# 1.net
KiCad netlist of a schematic drawn in Altium Designer
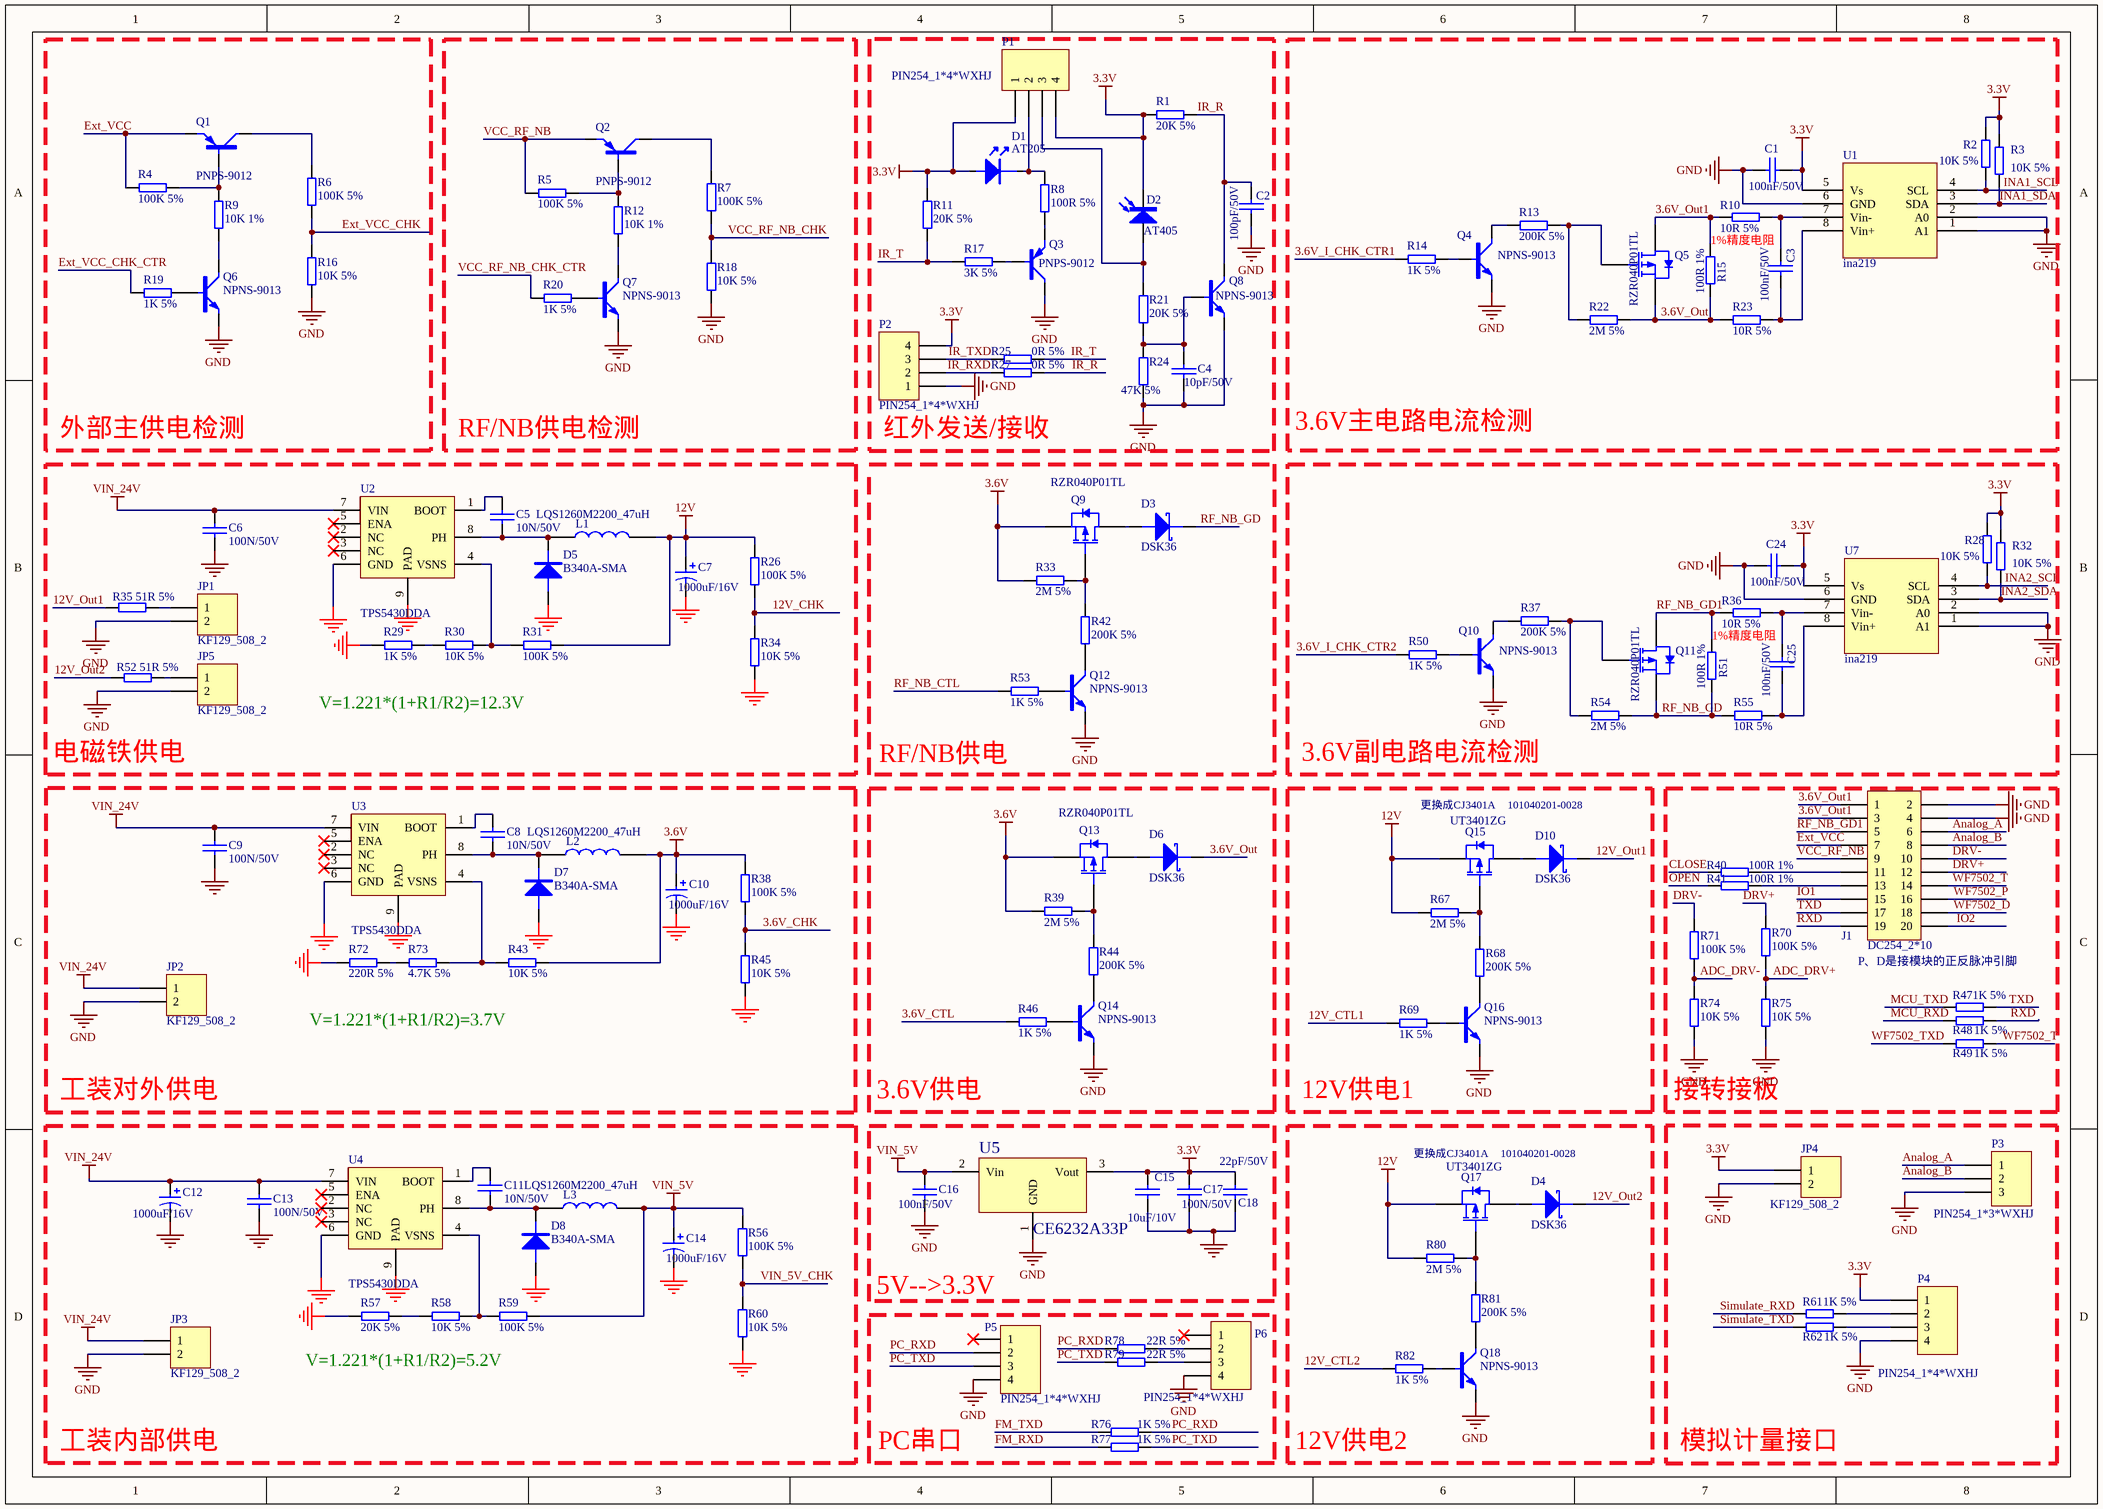
[diagram p0: 水表通用工装一版1.SchDoc]

(export (version "E")
  (design (tool "Eeschema 10.0.6"))
  (components
    (comp (ref "C1")
      (value "100nF/50V")
      (footprint "CAP0603")
      (description "104pF,50 V,±10%,0603,国巨,CC0603KRX7R9BB104")
      (fields (field (name "PART NUMBER") "101020103-0021"))
      (libsource (lib "Database_Libs2") (part "CC03K7R9_100N"))
    )
    (comp (ref "C2")
      (value "100pF/50V")
      (footprint "CAP0603")
      (description "101pf,50 V,±5%,0603,国巨,CC0603JRNP09BN101")
      (fields (field (name "PART NUMBER") "101020103-0010"))
      (libsource (lib "Database_Libs2") (part "CC03JPO9_101P"))
    )
    (comp (ref "C3")
      (value "100nF/50V")
      (footprint "CAP0603")
      (description "104pF,50 V,±10%,0603,国巨,CC0603KRX7R9BB104")
      (fields (field (name "PART NUMBER") "101020103-0021"))
      (libsource (lib "Database_Libs2") (part "CC03K7R9_100N"))
    )
    (comp (ref "C4")
      (value "10pF/50V")
      (footprint "CAP0603")
      (description "10pF,50 V,±5%,0603,X7R,国巨,CC0603JRNPO9BN100")
      (fields (field (name "PART NUMBER") "101020103-0014"))
      (libsource (lib "Database_Libs2") (part "CC03JPO9_10P"))
    )
    (comp (ref "C5")
      (value "10N/50V")
      (footprint "CAP0603")
      (description "10N/50V，±10%，0603")
      (fields (field (name "PART NUMBER") "101020103-0007"))
      (libsource (lib "Database_Libs1") (part "CC03K7R9B_10N"))
    )
    (comp (ref "C6")
      (value "100N/50V")
      (footprint "CAP0603")
      (description "100N/50V，±10%，0603")
      (fields (field (name "PART NUMBER") "101020103-0021"))
      (libsource (lib "Database_Libs1") (part "CC03K7R9B_100N"))
    )
    (comp (ref "C7")
      (value "1000uF/16V")
      (footprint "CAPPC_350_800_1600")
      (description "1000uF,16 V,±20%,8*20mm,Rubycon,16ZLH1000M")
      (fields (field (name "PART NUMBER") "1010203-0029"))
      (libsource (lib "Database_Libs2") (part "CAL7MRZLH_1000U_R"))
    )
    (comp (ref "C8")
      (value "10N/50V")
      (footprint "CAP0603")
      (description "10N/50V，±10%，0603")
      (fields (field (name "PART NUMBER") "101020103-0007"))
      (libsource (lib "Database_Libs1") (part "CC03K7R9B_10N"))
    )
    (comp (ref "C9")
      (value "100N/50V")
      (footprint "CAP0603")
      (description "100N/50V，±10%，0603")
      (fields (field (name "PART NUMBER") "101020103-0021"))
      (libsource (lib "Database_Libs1") (part "CC03K7R9B_100N"))
    )
    (comp (ref "C10")
      (value "1000uF/16V")
      (footprint "CAPPC_350_800_1600")
      (description "1000uF,16 V,±20%,8*20mm,Rubycon,16ZLH1000M")
      (fields (field (name "PART NUMBER") "1010203-0029"))
      (libsource (lib "Database_Libs2") (part "CAL7MRZLH_1000U_R"))
    )
    (comp (ref "C11")
      (value "10N/50V")
      (footprint "CAP0603")
      (description "10N/50V，±10%，0603")
      (fields (field (name "PART NUMBER") "101020103-0007"))
      (libsource (lib "Database_Libs1") (part "CC03K7R9B_10N"))
    )
    (comp (ref "C12")
      (value "1000uF/16V")
      (footprint "CAPPC_350_800_1600")
      (description "1000uF,16 V,±20%,8*20mm,Rubycon,16ZLH1000M")
      (fields (field (name "PART NUMBER") "1010203-0029"))
      (libsource (lib "Database_Libs2") (part "CAL7MRZLH_1000U_R"))
    )
    (comp (ref "C13")
      (value "100N/50V")
      (footprint "CAP0603")
      (description "100N/50V，±10%，0603")
      (fields (field (name "PART NUMBER") "101020103-0021"))
      (libsource (lib "Database_Libs1") (part "CC03K7R9B_100N"))
    )
    (comp (ref "C14")
      (value "1000uF/16V")
      (footprint "CAPPC_350_800_1600")
      (description "1000uF,16 V,±20%,8*20mm,Rubycon,16ZLH1000M")
      (fields (field (name "PART NUMBER") "1010203-0029"))
      (libsource (lib "Database_Libs2") (part "CAL7MRZLH_1000U_R"))
    )
    (comp (ref "C15")
      (value "10uF/10V")
      (footprint "CAP0603")
      (description "106pF,10 V,±10%,0603,村田,GRM188R61A106KE47D")
      (fields (field (name "PART NUMBER") "101020103-0026"))
      (libsource (lib "Database_Libs2") (part "CC03K5R6_10U"))
    )
    (comp (ref "C16")
      (value "100nF/50V")
      (footprint "CAP0603")
      (description "104pF,50 V,±10%,0603,国巨,CC0603KRX7R9BB104")
      (fields (field (name "PART NUMBER") "101020103-0021"))
      (libsource (lib "Database_Libs2") (part "CC03K7R9_100N"))
    )
    (comp (ref "C17")
      (value "100N/50V")
      (footprint "CAP0603")
      (description "100N/50V，±10%，0603")
      (fields (field (name "PART NUMBER") "101020103-0021"))
      (libsource (lib "Database_Libs2") (part "CC03K7R9B_100N"))
    )
    (comp (ref "C18")
      (value "22pF/50V")
      (footprint "CAP0603")
      (description "22pF,50 V,±5%,0603,国巨,CC0603JRNPO9BN22")
      (fields (field (name "PART NUMBER") "101020103-0009"))
      (libsource (lib "Database_Libs2") (part "CC03JPO9_22P"))
    )
    (comp (ref "C24")
      (value "100nF/50V")
      (footprint "CAP0603")
      (description "104pF,50 V,±10%,0603,国巨,CC0603KRX7R9BB104")
      (fields (field (name "PART NUMBER") "101020103-0021"))
      (libsource (lib "Database_Libs2") (part "CC03K7R9_100N"))
    )
    (comp (ref "C25")
      (value "100nF/50V")
      (footprint "CAP0603")
      (description "104pF,50 V,±10%,0603,国巨,CC0603KRX7R9BB104")
      (fields (field (name "PART NUMBER") "101020103-0021"))
      (libsource (lib "Database_Libs2") (part "CC03K7R9_100N"))
    )
    (comp (ref "D1") (value "AT205") (footprint "AT205/405") (libsource (lib "Schlib1") (part "AT205")))
    (comp (ref "D2")
      (value "AT405")
      (footprint "AT205/405")
      (description "红外接收头，插件，红光，AT405_PD_01")
      (fields (field (name "PART NUMBER") "101040102-0011") (field (name "MANUFACTURER") "品观"))
      (libsource (lib "Devices") (part "LED_IN"))
    )
    (comp (ref "D3")
      (value "DSK36")
      (footprint "SOD-123FL")
      (description "DSK14,SOD-123FL,1 A,40 V,28 V,台湾强茂集团苏州群鑫电子,DSK14")
      (fields (field (name "PART NUMBER") "101040101-0043"))
      (libsource (lib "Database_Libs2") (part "02_DSK14"))
    )
    (comp (ref "D4")
      (value "DSK36")
      (footprint "SOD-123FL")
      (description "DSK14,SOD-123FL,1 A,40 V,28 V,台湾强茂集团苏州群鑫电子,DSK14")
      (fields (field (name "PART NUMBER") "101040101-0043"))
      (libsource (lib "Database_Libs2") (part "02_DSK14"))
    )
    (comp (ref "D5")
      (value "B340A-SMA")
      (footprint "DO-214AC")
      (fields (field (name "PART NUMBER") "101040101-0014"))
      (libsource (lib "Database_Libs1") (part "02_B340A-SMA"))
    )
    (comp (ref "D6")
      (value "DSK36")
      (footprint "SOD-123FL")
      (description "DSK14,SOD-123FL,1 A,40 V,28 V,台湾强茂集团苏州群鑫电子,DSK14")
      (fields (field (name "PART NUMBER") "101040101-0043"))
      (libsource (lib "Database_Libs2") (part "02_DSK14"))
    )
    (comp (ref "D7")
      (value "B340A-SMA")
      (footprint "DO-214AC")
      (fields (field (name "PART NUMBER") "101040101-0014"))
      (libsource (lib "Database_Libs1") (part "02_B340A-SMA"))
    )
    (comp (ref "D8")
      (value "B340A-SMA")
      (footprint "DO-214AC")
      (fields (field (name "PART NUMBER") "101040101-0014"))
      (libsource (lib "Database_Libs1") (part "02_B340A-SMA"))
    )
    (comp (ref "D10")
      (value "DSK36")
      (footprint "SOD-123FL")
      (description "DSK14,SOD-123FL,1 A,40 V,28 V,台湾强茂集团苏州群鑫电子,DSK14")
      (fields (field (name "PART NUMBER") "101040101-0043"))
      (libsource (lib "Database_Libs2") (part "02_DSK14"))
    )
    (comp (ref "J1")
      (value "DC254_2*10")
      (footprint "DC254_2*10")
      (description "DC2 2.54mm 2x10pin,2.54mm间距，2x10pin，32×8.55×27.5mm,母头,双排,双排牛角座")
      (fields (field (name "PART NUMBER") "1010902-0139"))
      (libsource (lib "Database_Libs2") (part "DC254_2*10"))
    )
    (comp (ref "JP1")
      (value "KF129_508_2")
      (footprint "KF129_508_2")
      (description "KF129-2P,螺丝紧固,2,ABS,松涛")
      (fields (field (name "PART NUMBER") "1010904-0015"))
      (libsource (lib "Database_Libs2") (part "KF129_508_2"))
    )
    (comp (ref "JP2")
      (value "KF129_508_2")
      (footprint "KF129_508_2")
      (description "KF129-2P,螺丝紧固,2,ABS,松涛")
      (fields (field (name "PART NUMBER") "1010904-0015"))
      (libsource (lib "Database_Libs2") (part "KF129_508_2"))
    )
    (comp (ref "JP3")
      (value "KF129_508_2")
      (footprint "KF129_508_2")
      (description "KF129-2P,螺丝紧固,2,ABS,松涛")
      (fields (field (name "PART NUMBER") "1010904-0015"))
      (libsource (lib "Database_Libs2") (part "KF129_508_2"))
    )
    (comp (ref "JP4")
      (value "KF129_508_2")
      (footprint "KF129_508_2")
      (description "KF129-2P,螺丝紧固,2,ABS,松涛")
      (fields (field (name "PART NUMBER") "1010904-0015"))
      (libsource (lib "Database_Libs2") (part "KF129_508_2"))
    )
    (comp (ref "JP5")
      (value "KF129_508_2")
      (footprint "KF129_508_2")
      (description "KF129-2P,螺丝紧固,2,ABS,松涛")
      (fields (field (name "PART NUMBER") "1010904-0015"))
      (libsource (lib "Database_Libs2") (part "KF129_508_2"))
    )
    (comp (ref "L1")
      (value "LQS1260M2200_47uH")
      (footprint "LQS1212")
      (description "47uH/2.2A,±20%，0.072Ω，L1200X1200X600")
      (fields (field (name "PART NUMBER") "1010302-0007"))
      (libsource (lib "Database_Libs1") (part "06_LQS1260M2200_47uH"))
    )
    (comp (ref "L2")
      (value "LQS1260M2200_47uH")
      (footprint "LQS1212")
      (description "47uH/2.2A,±20%，0.072Ω，L1200X1200X600")
      (fields (field (name "PART NUMBER") "1010302-0007"))
      (libsource (lib "Database_Libs1") (part "06_LQS1260M2200_47uH"))
    )
    (comp (ref "L3")
      (value "LQS1260M2200_47uH")
      (footprint "LQS1212")
      (description "47uH/2.2A,±20%，0.072Ω，L1200X1200X600")
      (fields (field (name "PART NUMBER") "1010302-0007"))
      (libsource (lib "Database_Libs1") (part "06_LQS1260M2200_47uH"))
    )
    (comp (ref "P1")
      (value "PIN254_1*4*WXHJ")
      (footprint "PIN254_1*4*1100S")
      (description "1*4 ，Φ1.0 ，2.54mm，直脚,无需焊接器件")
      (fields (field (name "PART NUMBER") "AD_WXHJ_PinHeader_01"))
      (libsource (lib "") (part "PIN254_1*4*1100S_1"))
    )
    (comp (ref "P2")
      (value "PIN254_1*4*WXHJ")
      (footprint "PIN254_1*4*1100S")
      (description "1*4 ，Φ1.0 ，2.54mm，直脚,无需焊接器件")
      (fields (field (name "PART NUMBER") "AD_WXHJ_PinHeader_01"))
      (libsource (lib "Database_Libs2") (part "PIN254_1*4*1100S"))
    )
    (comp (ref "P3")
      (value "PIN254_1*3*WXHJ")
      (footprint "PIN254_1*3*1100S - duplicate")
      (description "1*3 ，Φ1.0 ，2.54mm，直脚,无需焊接器件")
      (fields (field (name "PART NUMBER") "AD_WXHJ_PinHeader_01"))
      (libsource (lib "模拟计量") (part "PIN254_1*3*1100S"))
    )
    (comp (ref "P4")
      (value "PIN254_1*4*WXHJ")
      (footprint "PIN254_1*4*1100S")
      (description "1*4 ，Φ1.0 ，2.54mm，直脚,无需焊接器件")
      (fields (field (name "PART NUMBER") "AD_WXHJ_PinHeader_01"))
      (libsource (lib "") (part "PIN254_1*4*1100S_2"))
    )
    (comp (ref "P5")
      (value "PIN254_1*4*WXHJ")
      (footprint "PIN254_1*4*1100S")
      (description "1*4 ，Φ1.0 ，2.54mm，直脚,无需焊接器件")
      (fields (field (name "PART NUMBER") "AD_WXHJ_PinHeader_01"))
      (libsource (lib "") (part "PIN254_1*4*1100S_2"))
    )
    (comp (ref "P6")
      (value "PIN254_1*4*WXHJ")
      (footprint "PIN254_1*4*1100S")
      (description "1*4 ，Φ1.0 ，2.54mm，直脚,无需焊接器件")
      (fields (field (name "PART NUMBER") "AD_WXHJ_PinHeader_01"))
      (libsource (lib "") (part "PIN254_1*4*1100S_2"))
    )
    (comp (ref "Q1")
      (value "PNPS-9012")
      (footprint "SOT-23")
      (description "9012,PNP,SOT-23,JCET;长电,S9012")
      (fields (field (name "PART NUMBER") "101040201-0001"))
      (libsource (lib "Database_Libs2") (part "03_PNPS-9012"))
    )
    (comp (ref "Q2")
      (value "PNPS-9012")
      (footprint "SOT-23")
      (description "9012,PNP,SOT-23,JCET;长电,S9012")
      (fields (field (name "PART NUMBER") "101040201-0001"))
      (libsource (lib "Database_Libs2") (part "03_PNPS-9012"))
    )
    (comp (ref "Q3")
      (value "PNPS-9012")
      (footprint "SOT-23")
      (description "9012,PNP,SOT-23,JCET;长电,S9012")
      (fields (field (name "PART NUMBER") "101040201-0001"))
      (libsource (lib "Database_Libs2") (part "03_PNPS-9012"))
    )
    (comp (ref "Q4")
      (value "NPNS-9013")
      (footprint "SOT-23")
      (description "9013,NPN,SOT-23,长电,S9013")
      (fields (field (name "PART NUMBER") "101040201-0002"))
      (libsource (lib "Database_Libs2") (part "03_NPNS-9013"))
    )
    (comp (ref "Q5")
      (value "RZR040P01TL")
      (footprint "SOT-23")
      (description "RZR040P01TL；1.5v导通,P-MOS,SOT-23,罗姆,RZR040P01TL")
      (fields (field (name "PART NUMBER") "101040201-0010"))
      (libsource (lib "Database_Libs2") (part "03_P-RZR040P01TL"))
    )
    (comp (ref "Q6")
      (value "NPNS-9013")
      (footprint "SOT-23")
      (description "9013,NPN,SOT-23,长电,S9013")
      (fields (field (name "PART NUMBER") "101040201-0002"))
      (libsource (lib "Database_Libs2") (part "03_NPNS-9013"))
    )
    (comp (ref "Q7")
      (value "NPNS-9013")
      (footprint "SOT-23")
      (description "9013,NPN,SOT-23,长电,S9013")
      (fields (field (name "PART NUMBER") "101040201-0002"))
      (libsource (lib "Database_Libs2") (part "03_NPNS-9013"))
    )
    (comp (ref "Q8")
      (value "NPNS-9013")
      (footprint "SOT-23")
      (description "9013,NPN,SOT-23,长电,S9013")
      (fields (field (name "PART NUMBER") "101040201-0002"))
      (libsource (lib "Database_Libs2") (part "03_NPNS-9013"))
    )
    (comp (ref "Q9")
      (value "RZR040P01TL")
      (footprint "SOT-23")
      (description "RZR040P01TL；1.5v导通,P-MOS,SOT-23,罗姆,RZR040P01TL")
      (fields (field (name "PART NUMBER") "101040201-0010"))
      (libsource (lib "Database_Libs2") (part "03_P-RZR040P01TL"))
    )
    (comp (ref "Q10")
      (value "NPNS-9013")
      (footprint "SOT-23")
      (description "9013,NPN,SOT-23,长电,S9013")
      (fields (field (name "PART NUMBER") "101040201-0002"))
      (libsource (lib "Database_Libs2") (part "03_NPNS-9013"))
    )
    (comp (ref "Q11")
      (value "RZR040P01TL")
      (footprint "SOT-23")
      (description "RZR040P01TL；1.5v导通,P-MOS,SOT-23,罗姆,RZR040P01TL")
      (fields (field (name "PART NUMBER") "101040201-0010"))
      (libsource (lib "Database_Libs2") (part "03_P-RZR040P01TL"))
    )
    (comp (ref "Q12")
      (value "NPNS-9013")
      (footprint "SOT-23")
      (description "9013,NPN,SOT-23,长电,S9013")
      (fields (field (name "PART NUMBER") "101040201-0002"))
      (libsource (lib "Database_Libs2") (part "03_NPNS-9013"))
    )
    (comp (ref "Q13")
      (value "RZR040P01TL")
      (footprint "SOT-23")
      (description "RZR040P01TL；1.5v导通,P-MOS,SOT-23,罗姆,RZR040P01TL")
      (fields (field (name "PART NUMBER") "101040201-0010"))
      (libsource (lib "Database_Libs2") (part "03_P-RZR040P01TL"))
    )
    (comp (ref "Q14")
      (value "NPNS-9013")
      (footprint "SOT-23")
      (description "9013,NPN,SOT-23,长电,S9013")
      (fields (field (name "PART NUMBER") "101040201-0002"))
      (libsource (lib "Database_Libs2") (part "03_NPNS-9013"))
    )
    (comp (ref "Q15")
      (value "UT3401ZG")
      (footprint "SOT-23")
      (description "UT3401ZG,P-MOS,SOT-23,UTC,UT3401ZG")
      (fields (field (name "PART NUMBER") "101040201-0013"))
      (libsource (lib "Database_Libs2") (part "03_P-UT3401ZG"))
    )
    (comp (ref "Q16")
      (value "NPNS-9013")
      (footprint "SOT-23")
      (description "9013,NPN,SOT-23,长电,S9013")
      (fields (field (name "PART NUMBER") "101040201-0002"))
      (libsource (lib "Database_Libs2") (part "03_NPNS-9013"))
    )
    (comp (ref "Q17")
      (value "UT3401ZG")
      (footprint "SOT-23")
      (description "UT3401ZG,P-MOS,SOT-23,UTC,UT3401ZG")
      (fields (field (name "PART NUMBER") "101040201-0013"))
      (libsource (lib "Database_Libs2") (part "03_P-UT3401ZG"))
    )
    (comp (ref "Q18")
      (value "NPNS-9013")
      (footprint "SOT-23")
      (description "9013,NPN,SOT-23,长电,S9013")
      (fields (field (name "PART NUMBER") "101040201-0002"))
      (libsource (lib "Database_Libs2") (part "03_NPNS-9013"))
    )
    (comp (ref "R1")
      (value "20K 5%")
      (footprint "RES0603")
      (description "国巨,±5%,0603,,155 ℃,-55 ℃,RC0603JR-0720KL,无铅,200 ppm/℃,1/10W,,20K")
      (fields (field (name "PART NUMBER") "101010103-0004"))
      (libsource (lib "Database_Libs2") (part "RC03J_20K"))
    )
    (comp (ref "R2")
      (value "10K 5%")
      (footprint "RES0603")
      (description "国巨,±5%,0603,,155 ℃,-55 ℃,RC0603JR-0710KL,无铅,200 ppm/℃,1/10W,,10K")
      (fields (field (name "PART NUMBER") "101010103-0003"))
      (libsource (lib "Database_Libs2") (part "RC03J_10K"))
    )
    (comp (ref "R3")
      (value "10K 5%")
      (footprint "RES0603")
      (description "国巨,±5%,0603,,155 ℃,-55 ℃,RC0603JR-0710KL,无铅,200 ppm/℃,1/10W,,10K")
      (fields (field (name "PART NUMBER") "101010103-0003"))
      (libsource (lib "Database_Libs2") (part "RC03J_10K"))
    )
    (comp (ref "R4")
      (value "100K 5%")
      (footprint "RES0603")
      (description "国巨,±5%,0603,,155 ℃,-55 ℃,RC0603JR-07100KL,无铅,100 ppm/℃,1/10W,,100K")
      (fields (field (name "PART NUMBER") "101010103-0005"))
      (libsource (lib "Database_Libs2") (part "RC03J_100K"))
    )
    (comp (ref "R5")
      (value "100K 5%")
      (footprint "RES0603")
      (description "国巨,±5%,0603,,155 ℃,-55 ℃,RC0603JR-07100KL,无铅,100 ppm/℃,1/10W,,100K")
      (fields (field (name "PART NUMBER") "101010103-0005"))
      (libsource (lib "Database_Libs2") (part "RC03J_100K"))
    )
    (comp (ref "R6")
      (value "100K 5%")
      (footprint "RES0603")
      (description "国巨,±5%,0603,,155 ℃,-55 ℃,RC0603JR-07100KL,无铅,100 ppm/℃,1/10W,,100K")
      (fields (field (name "PART NUMBER") "101010103-0005"))
      (libsource (lib "Database_Libs2") (part "RC03J_100K"))
    )
    (comp (ref "R7")
      (value "100K 5%")
      (footprint "RES0603")
      (description "国巨,±5%,0603,,155 ℃,-55 ℃,RC0603JR-07100KL,无铅,100 ppm/℃,1/10W,,100K")
      (fields (field (name "PART NUMBER") "101010103-0005"))
      (libsource (lib "Database_Libs2") (part "RC03J_100K"))
    )
    (comp (ref "R8")
      (value "100R 5%")
      (footprint "RES0603")
      (description "100R,±5%,1/10W,0603,国巨,RC0603JR-07100RL")
      (fields (field (name "PART NUMBER") "101010103-0022"))
      (libsource (lib "Database_Libs2") (part "RC03J_100R"))
    )
    (comp (ref "R9")
      (value "10K 1%")
      (footprint "RES0603")
      (description "10K±1%,1/10W,0603")
      (fields (field (name "PART NUMBER") "101010103-0052"))
      (libsource (lib "Database_Libs2") (part "RC03J_10K"))
    )
    (comp (ref "R10")
      (value "10R 5%")
      (footprint "RES0603")
      (description "10R,±5%,1/10W,0603,国巨,RC0603JR-0710RL")
      (fields (field (name "PART NUMBER") "101010103-0017"))
      (libsource (lib "Database_Libs2") (part "RC03J_10R"))
    )
    (comp (ref "R11")
      (value "20K 5%")
      (footprint "RES0603")
      (description "国巨,±5%,0603,,155 ℃,-55 ℃,RC0603JR-0720KL,无铅,200 ppm/℃,1/10W,,20K")
      (fields (field (name "PART NUMBER") "101010103-0004"))
      (libsource (lib "Database_Libs2") (part "RC03J_20K"))
    )
    (comp (ref "R12")
      (value "10K 1%")
      (footprint "RES0603")
      (description "10K±1%,1/10W,0603")
      (fields (field (name "PART NUMBER") "101010103-0052"))
      (libsource (lib "Database_Libs2") (part "RC03J_10K"))
    )
    (comp (ref "R13")
      (value "200K 5%")
      (footprint "RES0603")
      (description "200K,±5%,1/10W,0603,国巨,RC0603JR-07200KL")
      (fields (field (name "PART NUMBER") "101010103-0034"))
      (libsource (lib "Database_Libs2") (part "RC03J_200K"))
    )
    (comp (ref "R14")
      (value "1K 5%")
      (footprint "RES0603")
      (description "1K,±5%,1/10W,0603,国巨,RC0603JR-071KL")
      (fields (field (name "PART NUMBER") "101010103-0008"))
      (libsource (lib "Database_Libs2") (part "RC03J_1K"))
    )
    (comp (ref "R15")
      (value "100R 1%")
      (footprint "RES0603")
      (description "100Ω,±1%,1/10W,0603,国巨股份有限公司,RC0603FR-07100RL")
      (fields (field (name "PART NUMBER") "101010103-0041"))
      (libsource (lib "Database_Libs2") (part "RC03J_100R"))
    )
    (comp (ref "R16")
      (value "10K 5%")
      (footprint "RES0603")
      (description "国巨,±5%,0603,,155 ℃,-55 ℃,RC0603JR-0710KL,无铅,200 ppm/℃,1/10W,,10K")
      (fields (field (name "PART NUMBER") "101010103-0003"))
      (libsource (lib "Database_Libs2") (part "RC03J_10K"))
    )
    (comp (ref "R17")
      (value "3K 5%")
      (footprint "RES0603")
      (description "国巨,±5%,0603,,155 ℃,-55 ℃,RC0603JR-073KL,无铅,100 ppm/℃,1/10W,,3K")
      (fields (field (name "PART NUMBER") "101010103-0006"))
      (libsource (lib "Database_Libs2") (part "RC03J_3K"))
    )
    (comp (ref "R18")
      (value "10K 5%")
      (footprint "RES0603")
      (description "国巨,±5%,0603,,155 ℃,-55 ℃,RC0603JR-0710KL,无铅,200 ppm/℃,1/10W,,10K")
      (fields (field (name "PART NUMBER") "101010103-0003"))
      (libsource (lib "Database_Libs2") (part "RC03J_10K"))
    )
    (comp (ref "R19")
      (value "1K 5%")
      (footprint "RES0603")
      (description "1K,±5%,1/10W,0603,国巨,RC0603JR-071KL")
      (fields (field (name "PART NUMBER") "101010103-0008"))
      (libsource (lib "Database_Libs2") (part "RC03J_1K"))
    )
    (comp (ref "R20")
      (value "1K 5%")
      (footprint "RES0603")
      (description "1K,±5%,1/10W,0603,国巨,RC0603JR-071KL")
      (fields (field (name "PART NUMBER") "101010103-0008"))
      (libsource (lib "Database_Libs2") (part "RC03J_1K"))
    )
    (comp (ref "R21")
      (value "20K 5%")
      (footprint "RES0603")
      (description "国巨,±5%,0603,,155 ℃,-55 ℃,RC0603JR-0720KL,无铅,200 ppm/℃,1/10W,,20K")
      (fields (field (name "PART NUMBER") "101010103-0004"))
      (libsource (lib "Database_Libs2") (part "RC03J_20K"))
    )
    (comp (ref "R22")
      (value "2M 5%")
      (footprint "RES0603")
      (description "国巨,±5%,0603,,155 ℃,-55 ℃,RC0603JR-072ML,含铅,100 ppm/℃,1/10W,,2M")
      (fields (field (name "PART NUMBER") "101010103-0025"))
      (libsource (lib "Database_Libs2") (part "RC03J_2M"))
    )
    (comp (ref "R23")
      (value "10R 5%")
      (footprint "RES0603")
      (description "10R,±5%,1/10W,0603,国巨,RC0603JR-0710RL")
      (fields (field (name "PART NUMBER") "101010103-0017"))
      (libsource (lib "Database_Libs2") (part "RC03J_10R"))
    )
    (comp (ref "R24")
      (value "47K 5%")
      (footprint "RES0603")
      (description "47K,±5%,1/10W,0603,国巨,RC0603JR-0747KL")
      (fields (field (name "PART NUMBER") "101010103-0012"))
      (libsource (lib "Database_Libs2") (part "RC03J_47K"))
    )
    (comp (ref "R25")
      (value "0R 5%")
      (footprint "RES0603")
      (description "国巨,±5%,0603,,155 ℃,-55 ℃,RC0603J2-070RL,无铅,200 ppm/℃,1/10W,,0R")
      (fields (field (name "PART NUMBER") "101010103-0001"))
      (libsource (lib "Database_Libs2") (part "RC03J_0R"))
    )
    (comp (ref "R26")
      (value "100K 5%")
      (footprint "RES0603")
      (description "100K±5%,1/10W,0603")
      (fields (field (name "PART NUMBER") "101010103-0005"))
      (libsource (lib "Database_Libs1") (part "RC03JF_100K"))
    )
    (comp (ref "R27")
      (value "0R 5%")
      (footprint "RES0603")
      (description "国巨,±5%,0603,,155 ℃,-55 ℃,RC0603J2-070RL,无铅,200 ppm/℃,1/10W,,0R")
      (fields (field (name "PART NUMBER") "101010103-0001"))
      (libsource (lib "Database_Libs2") (part "RC03J_0R"))
    )
    (comp (ref "R28")
      (value "10K 5%")
      (footprint "RES0603")
      (description "国巨,±5%,0603,,155 ℃,-55 ℃,RC0603JR-0710KL,无铅,200 ppm/℃,1/10W,,10K")
      (fields (field (name "PART NUMBER") "101010103-0003"))
      (libsource (lib "Database_Libs2") (part "RC03J_10K"))
    )
    (comp (ref "R29")
      (value "1K 5%")
      (footprint "RES0603")
      (description "1K,±5%,1/10W,0603,国巨,RC0603JR-071KL")
      (fields (field (name "PART NUMBER") "101010103-0008"))
      (libsource (lib "Database_Libs2") (part "RC03J_1K"))
    )
    (comp (ref "R30")
      (value "10K 5%")
      (footprint "RES0603")
      (description "国巨,±5%,0603,,155 ℃,-55 ℃,RC0603JR-0710KL,无铅,200 ppm/℃,1/10W,,10K")
      (fields (field (name "PART NUMBER") "101010103-0003"))
      (libsource (lib "Database_Libs2") (part "RC03J_10K"))
    )
    (comp (ref "R31")
      (value "100K 5%")
      (footprint "RES0603")
      (description "国巨,±5%,0603,,155 ℃,-55 ℃,RC0603JR-07100KL,无铅,100 ppm/℃,1/10W,,100K")
      (fields (field (name "PART NUMBER") "101010103-0005"))
      (libsource (lib "Database_Libs2") (part "RC03J_100K"))
    )
    (comp (ref "R32")
      (value "10K 5%")
      (footprint "RES0603")
      (description "国巨,±5%,0603,,155 ℃,-55 ℃,RC0603JR-0710KL,无铅,200 ppm/℃,1/10W,,10K")
      (fields (field (name "PART NUMBER") "101010103-0003"))
      (libsource (lib "Database_Libs2") (part "RC03J_10K"))
    )
    (comp (ref "R33")
      (value "2M 5%")
      (footprint "RES0603")
      (description "国巨,±5%,0603,,155 ℃,-55 ℃,RC0603JR-072ML,含铅,100 ppm/℃,1/10W,,2M")
      (fields (field (name "PART NUMBER") "101010103-0025"))
      (libsource (lib "Database_Libs2") (part "RC03J_2M"))
    )
    (comp (ref "R34")
      (value "10K 5%")
      (footprint "RES0603")
      (description "国巨,±5%,0603,,155 ℃,-55 ℃,RC0603JR-0710KL,无铅,200 ppm/℃,1/10W,,10K")
      (fields (field (name "PART NUMBER") "101010103-0003"))
      (libsource (lib "Database_Libs2") (part "RC03J_10K"))
    )
    (comp (ref "R35")
      (value "51R 5%")
      (footprint "RES0603")
      (description "国巨,±5%,0603,,155 ℃,-55 ℃,RC0603JR-0751RL,无铅,100 ppm/℃,1/10W,,51欧")
      (fields (field (name "PART NUMBER") "101010103-0037"))
      (libsource (lib "Database_Libs2") (part "RC03J_51R"))
    )
    (comp (ref "R36")
      (value "10R 5%")
      (footprint "RES0603")
      (description "10R,±5%,1/10W,0603,国巨,RC0603JR-0710RL")
      (fields (field (name "PART NUMBER") "101010103-0017"))
      (libsource (lib "Database_Libs2") (part "RC03J_10R"))
    )
    (comp (ref "R37")
      (value "200K 5%")
      (footprint "RES0603")
      (description "200K,±5%,1/10W,0603,国巨,RC0603JR-07200KL")
      (fields (field (name "PART NUMBER") "101010103-0034"))
      (libsource (lib "Database_Libs2") (part "RC03J_200K"))
    )
    (comp (ref "R38")
      (value "100K 5%")
      (footprint "RES0603")
      (description "100K±5%,1/10W,0603")
      (fields (field (name "PART NUMBER") "101010103-0005"))
      (libsource (lib "Database_Libs1") (part "RC03JF_100K"))
    )
    (comp (ref "R39")
      (value "2M 5%")
      (footprint "RES0603")
      (description "国巨,±5%,0603,,155 ℃,-55 ℃,RC0603JR-072ML,含铅,100 ppm/℃,1/10W,,2M")
      (fields (field (name "PART NUMBER") "101010103-0025"))
      (libsource (lib "Database_Libs2") (part "RC03J_2M"))
    )
    (comp (ref "R40")
      (value "100R 1%")
      (footprint "RES0603")
      (description "100Ω,±1%,1/10W,0603,国巨股份有限公司,RC0603FR-07100RL")
      (fields (field (name "PART NUMBER") "101010103-0041"))
      (libsource (lib "Database_Libs2") (part "RC03J_100R"))
    )
    (comp (ref "R41")
      (value "100R 1%")
      (footprint "RES0603")
      (description "100Ω,±1%,1/10W,0603,国巨股份有限公司,RC0603FR-07100RL")
      (fields (field (name "PART NUMBER") "101010103-0041"))
      (libsource (lib "Database_Libs2") (part "RC03J_100R"))
    )
    (comp (ref "R42")
      (value "200K 5%")
      (footprint "RES0603")
      (description "200K,±5%,1/10W,0603,国巨,RC0603JR-07200KL")
      (fields (field (name "PART NUMBER") "101010103-0034"))
      (libsource (lib "Database_Libs2") (part "RC03J_200K"))
    )
    (comp (ref "R43")
      (value "10K 5%")
      (footprint "RES0603")
      (description "国巨,±5%,0603,,155 ℃,-55 ℃,RC0603JR-0710KL,无铅,200 ppm/℃,1/10W,,10K")
      (fields (field (name "PART NUMBER") "101010103-0003"))
      (libsource (lib "Database_Libs2") (part "RC03J_10K"))
    )
    (comp (ref "R44")
      (value "200K 5%")
      (footprint "RES0603")
      (description "200K,±5%,1/10W,0603,国巨,RC0603JR-07200KL")
      (fields (field (name "PART NUMBER") "101010103-0034"))
      (libsource (lib "Database_Libs2") (part "RC03J_200K"))
    )
    (comp (ref "R45")
      (value "10K 5%")
      (footprint "RES0603")
      (description "国巨,±5%,0603,,155 ℃,-55 ℃,RC0603JR-0710KL,无铅,200 ppm/℃,1/10W,,10K")
      (fields (field (name "PART NUMBER") "101010103-0003"))
      (libsource (lib "Database_Libs2") (part "RC03J_10K"))
    )
    (comp (ref "R46")
      (value "1K 5%")
      (footprint "RES0603")
      (description "1K,±5%,1/10W,0603,国巨,RC0603JR-071KL")
      (fields (field (name "PART NUMBER") "101010103-0008"))
      (libsource (lib "Database_Libs2") (part "RC03J_1K"))
    )
    (comp (ref "R47")
      (value "1K 5%")
      (footprint "RES0603")
      (description "1K,±5%,1/10W,0603,国巨,RC0603JR-071KL")
      (fields (field (name "PART NUMBER") "101010103-0008"))
      (libsource (lib "Database_Libs2") (part "RC03J_1K"))
    )
    (comp (ref "R48")
      (value "1K 5%")
      (footprint "RES0603")
      (description "1K,±5%,1/10W,0603,国巨,RC0603JR-071KL")
      (fields (field (name "PART NUMBER") "101010103-0008"))
      (libsource (lib "Database_Libs2") (part "RC03J_1K"))
    )
    (comp (ref "R49")
      (value "1K 5%")
      (footprint "RES0603")
      (description "1K,±5%,1/10W,0603,国巨,RC0603JR-071KL")
      (fields (field (name "PART NUMBER") "101010103-0008"))
      (libsource (lib "Database_Libs2") (part "RC03J_1K"))
    )
    (comp (ref "R50")
      (value "1K 5%")
      (footprint "RES0603")
      (description "1K,±5%,1/10W,0603,国巨,RC0603JR-071KL")
      (fields (field (name "PART NUMBER") "101010103-0008"))
      (libsource (lib "Database_Libs2") (part "RC03J_1K"))
    )
    (comp (ref "R51")
      (value "100R 1%")
      (footprint "RES0603")
      (description "100Ω,±1%,1/10W,0603,国巨股份有限公司,RC0603FR-07100RL")
      (fields (field (name "PART NUMBER") "101010103-0041"))
      (libsource (lib "Database_Libs2") (part "RC03J_100R"))
    )
    (comp (ref "R52")
      (value "51R 5%")
      (footprint "RES0603")
      (description "国巨,±5%,0603,,155 ℃,-55 ℃,RC0603JR-0751RL,无铅,100 ppm/℃,1/10W,,51欧")
      (fields (field (name "PART NUMBER") "101010103-0037"))
      (libsource (lib "Database_Libs2") (part "RC03J_51R"))
    )
    (comp (ref "R53")
      (value "1K 5%")
      (footprint "RES0603")
      (description "1K,±5%,1/10W,0603,国巨,RC0603JR-071KL")
      (fields (field (name "PART NUMBER") "101010103-0008"))
      (libsource (lib "Database_Libs2") (part "RC03J_1K"))
    )
    (comp (ref "R54")
      (value "2M 5%")
      (footprint "RES0603")
      (description "国巨,±5%,0603,,155 ℃,-55 ℃,RC0603JR-072ML,含铅,100 ppm/℃,1/10W,,2M")
      (fields (field (name "PART NUMBER") "101010103-0025"))
      (libsource (lib "Database_Libs2") (part "RC03J_2M"))
    )
    (comp (ref "R55")
      (value "10R 5%")
      (footprint "RES0603")
      (description "10R,±5%,1/10W,0603,国巨,RC0603JR-0710RL")
      (fields (field (name "PART NUMBER") "101010103-0017"))
      (libsource (lib "Database_Libs2") (part "RC03J_10R"))
    )
    (comp (ref "R56")
      (value "100K 5%")
      (footprint "RES0603")
      (description "100K±5%,1/10W,0603")
      (fields (field (name "PART NUMBER") "101010103-0005"))
      (libsource (lib "Database_Libs1") (part "RC03JF_100K"))
    )
    (comp (ref "R57")
      (value "20K 5%")
      (footprint "RES0603")
      (description "国巨,±5%,0603,,155 ℃,-55 ℃,RC0603JR-0720KL,无铅,200 ppm/℃,1/10W,,20K")
      (fields (field (name "PART NUMBER") "101010103-0004"))
      (libsource (lib "Database_Libs2") (part "RC03J_20K"))
    )
    (comp (ref "R58")
      (value "10K 5%")
      (footprint "RES0603")
      (description "国巨,±5%,0603,,155 ℃,-55 ℃,RC0603JR-0710KL,无铅,200 ppm/℃,1/10W,,10K")
      (fields (field (name "PART NUMBER") "101010103-0003"))
      (libsource (lib "Database_Libs2") (part "RC03J_10K"))
    )
    (comp (ref "R59")
      (value "100K 5%")
      (footprint "RES0603")
      (description "100K±5%,1/10W,0603")
      (fields (field (name "PART NUMBER") "101010103-0005"))
      (libsource (lib "Database_Libs1") (part "RC03JF_100K"))
    )
    (comp (ref "R60")
      (value "10K 5%")
      (footprint "RES0603")
      (description "国巨,±5%,0603,,155 ℃,-55 ℃,RC0603JR-0710KL,无铅,200 ppm/℃,1/10W,,10K")
      (fields (field (name "PART NUMBER") "101010103-0003"))
      (libsource (lib "Database_Libs2") (part "RC03J_10K"))
    )
    (comp (ref "R61")
      (value "1K 5%")
      (footprint "RES0603")
      (description "1K,±5%,1/10W,0603,国巨,RC0603JR-071KL")
      (fields (field (name "PART NUMBER") "101010103-0008"))
      (libsource (lib "Database_Libs2") (part "RC03J_1K"))
    )
    (comp (ref "R62")
      (value "1K 5%")
      (footprint "RES0603")
      (description "1K,±5%,1/10W,0603,国巨,RC0603JR-071KL")
      (fields (field (name "PART NUMBER") "101010103-0008"))
      (libsource (lib "Database_Libs2") (part "RC03J_1K"))
    )
    (comp (ref "R67")
      (value "2M 5%")
      (footprint "RES0603")
      (description "国巨,±5%,0603,,155 ℃,-55 ℃,RC0603JR-072ML,含铅,100 ppm/℃,1/10W,,2M")
      (fields (field (name "PART NUMBER") "101010103-0025"))
      (libsource (lib "Database_Libs2") (part "RC03J_2M"))
    )
    (comp (ref "R68")
      (value "200K 5%")
      (footprint "RES0603")
      (description "200K,±5%,1/10W,0603,国巨,RC0603JR-07200KL")
      (fields (field (name "PART NUMBER") "101010103-0034"))
      (libsource (lib "Database_Libs2") (part "RC03J_200K"))
    )
    (comp (ref "R69")
      (value "1K 5%")
      (footprint "RES0603")
      (description "1K,±5%,1/10W,0603,国巨,RC0603JR-071KL")
      (fields (field (name "PART NUMBER") "101010103-0008"))
      (libsource (lib "Database_Libs2") (part "RC03J_1K"))
    )
    (comp (ref "R70")
      (value "100K 5%")
      (footprint "RES0603")
      (description "100K±5%,1/10W,0603")
      (fields (field (name "PART NUMBER") "101010103-0005"))
      (libsource (lib "Database_Libs1") (part "RC03JF_100K"))
    )
    (comp (ref "R71")
      (value "100K 5%")
      (footprint "RES0603")
      (description "100K±5%,1/10W,0603")
      (fields (field (name "PART NUMBER") "101010103-0005"))
      (libsource (lib "Database_Libs1") (part "RC03JF_100K"))
    )
    (comp (ref "R72")
      (value "220R 5%")
      (footprint "RES0603")
      (description "220±5%,1/10W,0603,国巨,RC0603JR-07220RL")
      (fields (field (name "PART NUMBER") "101010103-0019"))
      (libsource (lib "Database_Libs2") (part "RC03J_220R"))
    )
    (comp (ref "R73")
      (value "4.7K 5%")
      (footprint "RES0603")
      (description "4.7K±5%,1/10W,0603")
      (fields (field (name "PART NUMBER") "101010103-0042"))
      (libsource (lib "Database_Libs2") (part "RC03J_4.7K"))
    )
    (comp (ref "R74")
      (value "10K 5%")
      (footprint "RES0603")
      (description "国巨,±5%,0603,,155 ℃,-55 ℃,RC0603JR-0710KL,无铅,200 ppm/℃,1/10W,,10K")
      (fields (field (name "PART NUMBER") "101010103-0003"))
      (libsource (lib "Database_Libs2") (part "RC03J_10K"))
    )
    (comp (ref "R75")
      (value "10K 5%")
      (footprint "RES0603")
      (description "国巨,±5%,0603,,155 ℃,-55 ℃,RC0603JR-0710KL,无铅,200 ppm/℃,1/10W,,10K")
      (fields (field (name "PART NUMBER") "101010103-0003"))
      (libsource (lib "Database_Libs2") (part "RC03J_10K"))
    )
    (comp (ref "R76")
      (value "1K 5%")
      (footprint "RES0603")
      (description "1K,±5%,1/10W,0603,国巨,RC0603JR-071KL")
      (fields (field (name "PART NUMBER") "101010103-0008"))
      (libsource (lib "Database_Libs2") (part "RC03J_1K"))
    )
    (comp (ref "R77")
      (value "1K 5%")
      (footprint "RES0603")
      (description "1K,±5%,1/10W,0603,国巨,RC0603JR-071KL")
      (fields (field (name "PART NUMBER") "101010103-0008"))
      (libsource (lib "Database_Libs2") (part "RC03J_1K"))
    )
    (comp (ref "R78")
      (value "22R 5%")
      (footprint "RES0603")
      (description "国巨,±5%,0603,,155 ℃,-55 ℃,RC0603JR-0722RL,无铅,200 ppm/℃,1/10W,,22欧")
      (fields (field (name "PART NUMBER") "101010103-0009"))
      (libsource (lib "Database_Libs2") (part "RC03J_22R"))
    )
    (comp (ref "R79")
      (value "22R 5%")
      (footprint "RES0603")
      (description "国巨,±5%,0603,,155 ℃,-55 ℃,RC0603JR-0722RL,无铅,200 ppm/℃,1/10W,,22欧")
      (fields (field (name "PART NUMBER") "101010103-0009"))
      (libsource (lib "Database_Libs2") (part "RC03J_22R"))
    )
    (comp (ref "R80")
      (value "2M 5%")
      (footprint "RES0603")
      (description "国巨,±5%,0603,,155 ℃,-55 ℃,RC0603JR-072ML,含铅,100 ppm/℃,1/10W,,2M")
      (fields (field (name "PART NUMBER") "101010103-0025"))
      (libsource (lib "Database_Libs2") (part "RC03J_2M"))
    )
    (comp (ref "R81")
      (value "200K 5%")
      (footprint "RES0603")
      (description "200K,±5%,1/10W,0603,国巨,RC0603JR-07200KL")
      (fields (field (name "PART NUMBER") "101010103-0034"))
      (libsource (lib "Database_Libs2") (part "RC03J_200K"))
    )
    (comp (ref "R82")
      (value "1K 5%")
      (footprint "RES0603")
      (description "1K,±5%,1/10W,0603,国巨,RC0603JR-071KL")
      (fields (field (name "PART NUMBER") "101010103-0008"))
      (libsource (lib "Database_Libs2") (part "RC03J_1K"))
    )
    (comp (ref "U1") (value "ina219") (footprint "SO-8") (libsource (lib "Schlib1") (part "Component_2")))
    (comp (ref "U2")
      (value "TPS5430DDA")
      (footprint "SOP-8-P")
      (description "TPS5430DDA,SOP8,TI,TPS5430DDA")
      (fields (field (name "PART NUMBER") "101050101-0053"))
      (libsource (lib "Database_Libs2") (part "02_TPS5430DDA"))
    )
    (comp (ref "U3")
      (value "TPS5430DDA")
      (footprint "SOP-8-P")
      (description "TPS5430DDA,SOP8,TI,TPS5430DDA")
      (fields (field (name "PART NUMBER") "101050101-0053"))
      (libsource (lib "Database_Libs2") (part "02_TPS5430DDA"))
    )
    (comp (ref "U4")
      (value "TPS5430DDA")
      (footprint "SOP-8-P")
      (description "TPS5430DDA,SOP8,TI,TPS5430DDA")
      (fields (field (name "PART NUMBER") "101050101-0053"))
      (libsource (lib "Database_Libs2") (part "02_TPS5430DDA"))
    )
    (comp (ref "U5")
      (value "CE6232A33P")
      (footprint "SOT-89")
      (description "CE6232-3.3,CE6232-3.3,SOT89-3,8V,1.8V,0.11V,3.3V,300mA,0.8uA,南京芯力微电子有限公司")
      (fields (field (name "PART NUMBER") "1010503-0029"))
      (libsource (lib "Database_Libs2") (part "02_CE6232A33P"))
    )
    (comp (ref "U7") (value "ina219") (footprint "SO-8") (libsource (lib "Schlib1") (part "Component_2")))
  )
  (nets
    (net (code "1") (name "/3.6V_CHK") (class "Default")
      (node (ref "R38") (pin "1") (pinfunction "1_1") (pintype "passive"))
      (node (ref "R45") (pin "2") (pinfunction "2_2") (pintype "passive"))
    )
    (net (code "2") (name "/3.6V_CTL") (class "Default")
      (node (ref "R46") (pin "1") (pinfunction "1_1") (pintype "passive"))
    )
    (net (code "3") (name "/3.6V_I_CHK_CTR1") (class "Default")
      (node (ref "R14") (pin "2") (pinfunction "2_2") (pintype "passive"))
    )
    (net (code "4") (name "/3.6V_I_CHK_CTR2") (class "Default")
      (node (ref "R50") (pin "2") (pinfunction "2_2") (pintype "passive"))
    )
    (net (code "5") (name "/3.6V_Out") (class "Default")
      (node (ref "D6") (pin "2") (pinfunction "2_2") (pintype "passive"))
      (node (ref "Q5") (pin "2") (pinfunction "S_2") (pintype "passive"))
      (node (ref "R15") (pin "1") (pinfunction "1_1") (pintype "passive"))
      (node (ref "R22") (pin "2") (pinfunction "2_2") (pintype "passive"))
      (node (ref "R23") (pin "1") (pinfunction "1_1") (pintype "passive"))
    )
    (net (code "6") (name "/3.6V_Out1") (class "Default")
      (node (ref "J1") (pin "1") (pinfunction "1_1") (pintype "passive"))
      (node (ref "J1") (pin "3") (pinfunction "3_3") (pintype "passive"))
      (node (ref "Q5") (pin "3") (pinfunction "D_3") (pintype "passive"))
      (node (ref "R10") (pin "1") (pinfunction "1_1") (pintype "passive"))
      (node (ref "R15") (pin "2") (pinfunction "2_2") (pintype "passive"))
    )
    (net (code "7") (name "/12V_CHK") (class "Default")
      (node (ref "R26") (pin "1") (pinfunction "1_1") (pintype "passive"))
      (node (ref "R34") (pin "2") (pinfunction "2_2") (pintype "passive"))
    )
    (net (code "8") (name "/12V_CTL1") (class "Default")
      (node (ref "R69") (pin "1") (pinfunction "1_1") (pintype "passive"))
    )
    (net (code "9") (name "/12V_CTL2") (class "Default")
      (node (ref "R82") (pin "1") (pinfunction "1_1") (pintype "passive"))
    )
    (net (code "10") (name "/12V_Out1") (class "Default")
      (node (ref "D10") (pin "2") (pinfunction "2_2") (pintype "passive"))
      (node (ref "R35") (pin "1") (pinfunction "1_1") (pintype "passive"))
    )
    (net (code "11") (name "/12V_Out2") (class "Default")
      (node (ref "D4") (pin "2") (pinfunction "2_2") (pintype "passive"))
      (node (ref "R52") (pin "1") (pinfunction "1_1") (pintype "passive"))
    )
    (net (code "12") (name "/ADC_DRV+") (class "Default")
      (node (ref "R70") (pin "1") (pinfunction "1_1") (pintype "passive"))
      (node (ref "R75") (pin "2") (pinfunction "2_2") (pintype "passive"))
    )
    (net (code "13") (name "/ADC_DRV-") (class "Default")
      (node (ref "R71") (pin "1") (pinfunction "1_1") (pintype "passive"))
      (node (ref "R74") (pin "2") (pinfunction "2_2") (pintype "passive"))
    )
    (net (code "14") (name "/Analog_A") (class "Default")
      (node (ref "J1") (pin "6") (pinfunction "6_6") (pintype "passive"))
      (node (ref "P3") (pin "1") (pinfunction "1_1") (pintype "passive"))
    )
    (net (code "15") (name "/Analog_B") (class "Default")
      (node (ref "J1") (pin "8") (pinfunction "8_8") (pintype "passive"))
      (node (ref "P3") (pin "2") (pinfunction "2_2") (pintype "passive"))
    )
    (net (code "16") (name "/CLOSE") (class "Default")
      (node (ref "R40") (pin "1") (pinfunction "1_1") (pintype "passive"))
    )
    (net (code "17") (name "/DRV+") (class "Default")
      (node (ref "J1") (pin "12") (pinfunction "12_12") (pintype "passive"))
      (node (ref "R70") (pin "2") (pinfunction "2_2") (pintype "passive"))
    )
    (net (code "18") (name "/DRV-") (class "Default")
      (node (ref "J1") (pin "10") (pinfunction "10_10") (pintype "passive"))
      (node (ref "R71") (pin "2") (pinfunction "2_2") (pintype "passive"))
    )
    (net (code "19") (name "/Ext_VCC") (class "Default")
      (node (ref "J1") (pin "7") (pinfunction "7_7") (pintype "passive"))
      (node (ref "Q1") (pin "2") (pinfunction "E_2") (pintype "passive"))
      (node (ref "R4") (pin "2") (pinfunction "2_2") (pintype "passive"))
    )
    (net (code "20") (name "/Ext_VCC_CHK") (class "Default")
      (node (ref "R16") (pin "1") (pinfunction "1_1") (pintype "passive"))
      (node (ref "R6") (pin "2") (pinfunction "2_2") (pintype "passive"))
    )
    (net (code "21") (name "/Ext_VCC_CHK_CTR") (class "Default")
      (node (ref "R19") (pin "1") (pinfunction "1_1") (pintype "passive"))
    )
    (net (code "22") (name "/FM_RXD") (class "Default")
      (node (ref "R77") (pin "1") (pinfunction "1_1") (pintype "passive"))
    )
    (net (code "23") (name "/FM_TXD") (class "Default")
      (node (ref "R76") (pin "1") (pinfunction "1_1") (pintype "passive"))
    )
    (net (code "24") (name "/INA1_SCL") (class "Default")
      (node (ref "R2") (pin "2") (pinfunction "2_2") (pintype "passive"))
      (node (ref "U1") (pin "4") (pinfunction "SCL_4") (pintype "passive"))
    )
    (net (code "25") (name "/INA1_SDA") (class "Default")
      (node (ref "R3") (pin "2") (pinfunction "2_2") (pintype "passive"))
      (node (ref "U1") (pin "3") (pinfunction "SDA_3") (pintype "passive"))
    )
    (net (code "26") (name "/INA2_SCL") (class "Default")
      (node (ref "R28") (pin "2") (pinfunction "2_2") (pintype "passive"))
      (node (ref "U7") (pin "4") (pinfunction "SCL_4") (pintype "passive"))
    )
    (net (code "27") (name "/INA2_SDA") (class "Default")
      (node (ref "R32") (pin "2") (pinfunction "2_2") (pintype "passive"))
      (node (ref "U7") (pin "3") (pinfunction "SDA_3") (pintype "passive"))
    )
    (net (code "28") (name "/IO1") (class "Default")
      (node (ref "J1") (pin "15") (pinfunction "15_15") (pintype "passive"))
    )
    (net (code "29") (name "/IO2") (class "Default")
      (node (ref "J1") (pin "20") (pinfunction "20_20") (pintype "passive"))
    )
    (net (code "30") (name "/IR_R") (class "Default")
      (node (ref "C2") (pin "1") (pinfunction "1_1") (pintype "passive"))
      (node (ref "Q8") (pin "3") (pinfunction "C_3") (pintype "passive"))
      (node (ref "R1") (pin "2") (pinfunction "2_2") (pintype "passive"))
      (node (ref "R27") (pin "2") (pinfunction "2_2") (pintype "passive"))
    )
    (net (code "31") (name "/IR_RXD") (class "Default")
      (node (ref "P2") (pin "2") (pinfunction "2_2") (pintype "passive"))
      (node (ref "R27") (pin "1") (pinfunction "1_1") (pintype "passive"))
    )
    (net (code "32") (name "/IR_T") (class "Default")
      (node (ref "R11") (pin "1") (pinfunction "1_1") (pintype "passive"))
      (node (ref "R17") (pin "1") (pinfunction "1_1") (pintype "passive"))
      (node (ref "R25") (pin "2") (pinfunction "2_2") (pintype "passive"))
    )
    (net (code "33") (name "/IR_TXD") (class "Default")
      (node (ref "P2") (pin "3") (pinfunction "3_3") (pintype "passive"))
      (node (ref "R25") (pin "1") (pinfunction "1_1") (pintype "passive"))
    )
    (net (code "34") (name "/MCU_RXD") (class "Default")
      (node (ref "R48") (pin "1") (pinfunction "1_1") (pintype "passive"))
    )
    (net (code "35") (name "/MCU_TXD") (class "Default")
      (node (ref "R47") (pin "1") (pinfunction "1_1") (pintype "passive"))
    )
    (net (code "36") (name "/OPEN") (class "Default")
      (node (ref "R41") (pin "1") (pinfunction "1_1") (pintype "passive"))
    )
    (net (code "37") (name "/PC_RXD") (class "Default")
      (node (ref "P5") (pin "2") (pinfunction "2_2") (pintype "passive"))
      (node (ref "R76") (pin "2") (pinfunction "2_2") (pintype "passive"))
      (node (ref "R78") (pin "1") (pinfunction "1_1") (pintype "passive"))
    )
    (net (code "38") (name "/PC_TXD") (class "Default")
      (node (ref "P5") (pin "3") (pinfunction "3_3") (pintype "passive"))
      (node (ref "R77") (pin "2") (pinfunction "2_2") (pintype "passive"))
      (node (ref "R79") (pin "1") (pinfunction "1_1") (pintype "passive"))
    )
    (net (code "39") (name "/RF_NB_CTL") (class "Default")
      (node (ref "R53") (pin "1") (pinfunction "1_1") (pintype "passive"))
    )
    (net (code "40") (name "/RF_NB_GD") (class "Default")
      (node (ref "D3") (pin "2") (pinfunction "2_2") (pintype "passive"))
      (node (ref "Q11") (pin "2") (pinfunction "S_2") (pintype "passive"))
      (node (ref "R51") (pin "1") (pinfunction "1_1") (pintype "passive"))
      (node (ref "R54") (pin "2") (pinfunction "2_2") (pintype "passive"))
      (node (ref "R55") (pin "1") (pinfunction "1_1") (pintype "passive"))
    )
    (net (code "41") (name "/RF_NB_GD1") (class "Default")
      (node (ref "J1") (pin "5") (pinfunction "5_5") (pintype "passive"))
      (node (ref "Q11") (pin "3") (pinfunction "D_3") (pintype "passive"))
      (node (ref "R36") (pin "1") (pinfunction "1_1") (pintype "passive"))
      (node (ref "R51") (pin "2") (pinfunction "2_2") (pintype "passive"))
    )
    (net (code "42") (name "/RXD") (class "Default")
      (node (ref "J1") (pin "19") (pinfunction "19_19") (pintype "passive"))
      (node (ref "R48") (pin "2") (pinfunction "2_2") (pintype "passive"))
    )
    (net (code "43") (name "/Simulate_RXD") (class "Default")
      (node (ref "R61") (pin "1") (pinfunction "1_1") (pintype "passive"))
    )
    (net (code "44") (name "/Simulate_TXD") (class "Default")
      (node (ref "R62") (pin "1") (pinfunction "1_1") (pintype "passive"))
    )
    (net (code "45") (name "/TXD") (class "Default")
      (node (ref "J1") (pin "17") (pinfunction "17_17") (pintype "passive"))
      (node (ref "R47") (pin "2") (pinfunction "2_2") (pintype "passive"))
    )
    (net (code "46") (name "/VCC_RF_NB") (class "Default")
      (node (ref "J1") (pin "9") (pinfunction "9_9") (pintype "passive"))
      (node (ref "Q2") (pin "2") (pinfunction "E_2") (pintype "passive"))
      (node (ref "R5") (pin "2") (pinfunction "2_2") (pintype "passive"))
    )
    (net (code "47") (name "/VCC_RF_NB_CHK") (class "Default")
      (node (ref "R18") (pin "1") (pinfunction "1_1") (pintype "passive"))
      (node (ref "R7") (pin "2") (pinfunction "2_2") (pintype "passive"))
    )
    (net (code "48") (name "/VCC_RF_NB_CHK_CTR") (class "Default")
      (node (ref "R20") (pin "1") (pinfunction "1_1") (pintype "passive"))
    )
    (net (code "49") (name "/VIN_5V_CHK") (class "Default")
      (node (ref "R56") (pin "1") (pinfunction "1_1") (pintype "passive"))
      (node (ref "R60") (pin "2") (pinfunction "2_2") (pintype "passive"))
    )
    (net (code "50") (name "/WF7502_D") (class "Default")
      (node (ref "J1") (pin "18") (pinfunction "18_18") (pintype "passive"))
    )
    (net (code "51") (name "/WF7502_P") (class "Default")
      (node (ref "J1") (pin "16") (pinfunction "16_16") (pintype "passive"))
    )
    (net (code "52") (name "/WF7502_T") (class "Default")
      (node (ref "J1") (pin "14") (pinfunction "14_14") (pintype "passive"))
      (node (ref "R49") (pin "2") (pinfunction "2_2") (pintype "passive"))
    )
    (net (code "53") (name "/WF7502_TXD") (class "Default")
      (node (ref "R49") (pin "1") (pinfunction "1_1") (pintype "passive"))
    )
    (net (code "54") (name "3.3V") (class "Default")
      (node (ref "C1") (pin "2") (pinfunction "2_2") (pintype "passive"))
      (node (ref "C15") (pin "1") (pinfunction "1_1") (pintype "passive"))
      (node (ref "C17") (pin "1") (pinfunction "1_1") (pintype "passive"))
      (node (ref "C18") (pin "1") (pinfunction "1_1") (pintype "passive"))
      (node (ref "C24") (pin "2") (pinfunction "2_2") (pintype "passive"))
      (node (ref "D1") (pin "1") (pinfunction "1_1") (pintype "passive"))
      (node (ref "D2") (pin "2") (pinfunction "K_2") (pintype "passive"))
      (node (ref "JP4") (pin "1") (pinfunction "1_1") (pintype "passive"))
      (node (ref "P1") (pin "1") (pinfunction "1_1") (pintype "passive"))
      (node (ref "P1") (pin "4") (pinfunction "4_4") (pintype "passive"))
      (node (ref "P2") (pin "4") (pinfunction "4_4") (pintype "passive"))
      (node (ref "P4") (pin "1") (pinfunction "1_1") (pintype "passive"))
      (node (ref "R1") (pin "1") (pinfunction "1_1") (pintype "passive"))
      (node (ref "R11") (pin "2") (pinfunction "2_2") (pintype "passive"))
      (node (ref "R2") (pin "1") (pinfunction "1_1") (pintype "passive"))
      (node (ref "R28") (pin "1") (pinfunction "1_1") (pintype "passive"))
      (node (ref "R3") (pin "1") (pinfunction "1_1") (pintype "passive"))
      (node (ref "R32") (pin "1") (pinfunction "1_1") (pintype "passive"))
      (node (ref "U1") (pin "5") (pinfunction "Vs_5") (pintype "passive"))
      (node (ref "U5") (pin "3") (pinfunction "Vout_3") (pintype "passive"))
      (node (ref "U7") (pin "5") (pinfunction "Vs_5") (pintype "passive"))
    )
    (net (code "55") (name "3.6V") (class "Default")
      (node (ref "C10") (pin "1") (pinfunction "1_1") (pintype "passive"))
      (node (ref "L2") (pin "2") (pinfunction "2_2") (pintype "passive"))
      (node (ref "Q13") (pin "2") (pinfunction "S_2") (pintype "passive"))
      (node (ref "Q9") (pin "2") (pinfunction "S_2") (pintype "passive"))
      (node (ref "R33") (pin "1") (pinfunction "1_1") (pintype "passive"))
      (node (ref "R38") (pin "2") (pinfunction "2_2") (pintype "passive"))
      (node (ref "R39") (pin "1") (pinfunction "1_1") (pintype "passive"))
      (node (ref "R43") (pin "2") (pinfunction "2_2") (pintype "passive"))
    )
    (net (code "56") (name "12V") (class "Default")
      (node (ref "C7") (pin "1") (pinfunction "1_1") (pintype "passive"))
      (node (ref "L1") (pin "2") (pinfunction "2_2") (pintype "passive"))
      (node (ref "Q15") (pin "2") (pinfunction "S_2") (pintype "passive"))
      (node (ref "Q17") (pin "2") (pinfunction "S_2") (pintype "passive"))
      (node (ref "R26") (pin "2") (pinfunction "2_2") (pintype "passive"))
      (node (ref "R31") (pin "2") (pinfunction "2_2") (pintype "passive"))
      (node (ref "R67") (pin "1") (pinfunction "1_1") (pintype "passive"))
      (node (ref "R80") (pin "1") (pinfunction "1_1") (pintype "passive"))
    )
    (net (code "57") (name "GND") (class "Default")
      (node (ref "C1") (pin "1") (pinfunction "1_1") (pintype "passive"))
      (node (ref "C10") (pin "2") (pinfunction "2_2") (pintype "passive"))
      (node (ref "C12") (pin "2") (pinfunction "2_2") (pintype "passive"))
      (node (ref "C13") (pin "2") (pinfunction "2_2") (pintype "passive"))
      (node (ref "C14") (pin "2") (pinfunction "2_2") (pintype "passive"))
      (node (ref "C15") (pin "2") (pinfunction "2_2") (pintype "passive"))
      (node (ref "C16") (pin "2") (pinfunction "2_2") (pintype "passive"))
      (node (ref "C17") (pin "2") (pinfunction "2_2") (pintype "passive"))
      (node (ref "C18") (pin "2") (pinfunction "2_2") (pintype "passive"))
      (node (ref "C2") (pin "2") (pinfunction "2_2") (pintype "passive"))
      (node (ref "C24") (pin "1") (pinfunction "1_1") (pintype "passive"))
      (node (ref "C4") (pin "2") (pinfunction "2_2") (pintype "passive"))
      (node (ref "C6") (pin "2") (pinfunction "2_2") (pintype "passive"))
      (node (ref "C7") (pin "2") (pinfunction "2_2") (pintype "passive"))
      (node (ref "C9") (pin "2") (pinfunction "2_2") (pintype "passive"))
      (node (ref "D5") (pin "1") (pinfunction "1_1") (pintype "passive"))
      (node (ref "D7") (pin "1") (pinfunction "1_1") (pintype "passive"))
      (node (ref "D8") (pin "1") (pinfunction "1_1") (pintype "passive"))
      (node (ref "J1") (pin "2") (pinfunction "2_2") (pintype "passive"))
      (node (ref "J1") (pin "4") (pinfunction "4_4") (pintype "passive"))
      (node (ref "JP1") (pin "2") (pinfunction "2_2") (pintype "passive"))
      (node (ref "JP2") (pin "2") (pinfunction "2_2") (pintype "passive"))
      (node (ref "JP3") (pin "2") (pinfunction "2_2") (pintype "passive"))
      (node (ref "JP4") (pin "2") (pinfunction "2_2") (pintype "passive"))
      (node (ref "JP5") (pin "2") (pinfunction "2_2") (pintype "passive"))
      (node (ref "P2") (pin "1") (pinfunction "1_1") (pintype "passive"))
      (node (ref "P3") (pin "3") (pinfunction "3_3") (pintype "passive"))
      (node (ref "P4") (pin "4") (pinfunction "4_4") (pintype "passive"))
      (node (ref "P5") (pin "4") (pinfunction "4_4") (pintype "passive"))
      (node (ref "P6") (pin "4") (pinfunction "4_4") (pintype "passive"))
      (node (ref "Q10") (pin "2") (pinfunction "E_2") (pintype "passive"))
      (node (ref "Q12") (pin "2") (pinfunction "E_2") (pintype "passive"))
      (node (ref "Q14") (pin "2") (pinfunction "E_2") (pintype "passive"))
      (node (ref "Q16") (pin "2") (pinfunction "E_2") (pintype "passive"))
      (node (ref "Q18") (pin "2") (pinfunction "E_2") (pintype "passive"))
      (node (ref "Q3") (pin "3") (pinfunction "C_3") (pintype "passive"))
      (node (ref "Q4") (pin "2") (pinfunction "E_2") (pintype "passive"))
      (node (ref "Q6") (pin "2") (pinfunction "E_2") (pintype "passive"))
      (node (ref "Q7") (pin "2") (pinfunction "E_2") (pintype "passive"))
      (node (ref "Q8") (pin "2") (pinfunction "E_2") (pintype "passive"))
      (node (ref "R16") (pin "2") (pinfunction "2_2") (pintype "passive"))
      (node (ref "R18") (pin "2") (pinfunction "2_2") (pintype "passive"))
      (node (ref "R24") (pin "1") (pinfunction "1_1") (pintype "passive"))
      (node (ref "R29") (pin "1") (pinfunction "1_1") (pintype "passive"))
      (node (ref "R34") (pin "1") (pinfunction "1_1") (pintype "passive"))
      (node (ref "R45") (pin "1") (pinfunction "1_1") (pintype "passive"))
      (node (ref "R57") (pin "1") (pinfunction "1_1") (pintype "passive"))
      (node (ref "R60") (pin "1") (pinfunction "1_1") (pintype "passive"))
      (node (ref "R72") (pin "1") (pinfunction "1_1") (pintype "passive"))
      (node (ref "R74") (pin "1") (pinfunction "1_1") (pintype "passive"))
      (node (ref "R75") (pin "1") (pinfunction "1_1") (pintype "passive"))
      (node (ref "U1") (pin "1") (pinfunction "A1_1") (pintype "passive"))
      (node (ref "U1") (pin "2") (pinfunction "A0_2") (pintype "passive"))
      (node (ref "U1") (pin "6") (pinfunction "GND_6") (pintype "passive"))
      (node (ref "U2") (pin "6") (pinfunction "GND_6") (pintype "passive"))
      (node (ref "U2") (pin "9") (pinfunction "PAD_9") (pintype "passive"))
      (node (ref "U3") (pin "6") (pinfunction "GND_6") (pintype "passive"))
      (node (ref "U3") (pin "9") (pinfunction "PAD_9") (pintype "passive"))
      (node (ref "U4") (pin "6") (pinfunction "GND_6") (pintype "passive"))
      (node (ref "U4") (pin "9") (pinfunction "PAD_9") (pintype "passive"))
      (node (ref "U5") (pin "1") (pinfunction "GND_1") (pintype "passive"))
      (node (ref "U7") (pin "1") (pinfunction "A1_1") (pintype "passive"))
      (node (ref "U7") (pin "2") (pinfunction "A0_2") (pintype "passive"))
      (node (ref "U7") (pin "6") (pinfunction "GND_6") (pintype "passive"))
    )
    (net (code "58") (name "Net-(D1-Pad2)") (class "Default")
      (node (ref "D1") (pin "2") (pinfunction "2_2") (pintype "passive"))
      (node (ref "P1") (pin "2") (pinfunction "2_2") (pintype "passive"))
      (node (ref "R8") (pin "2") (pinfunction "2_2") (pintype "passive"))
    )
    (net (code "59") (name "Net-(D2-A)") (class "Default")
      (node (ref "D2") (pin "1") (pinfunction "A_1") (pintype "passive"))
      (node (ref "P1") (pin "3") (pinfunction "3_3") (pintype "passive"))
      (node (ref "R21") (pin "2") (pinfunction "2_2") (pintype "passive"))
    )
    (net (code "60") (name "Net-(J1-Pad11)") (class "Default")
      (node (ref "J1") (pin "11") (pinfunction "11_11") (pintype "passive"))
      (node (ref "R40") (pin "2") (pinfunction "2_2") (pintype "passive"))
    )
    (net (code "61") (name "Net-(J1-Pad13)") (class "Default")
      (node (ref "J1") (pin "13") (pinfunction "13_13") (pintype "passive"))
      (node (ref "R41") (pin "2") (pinfunction "2_2") (pintype "passive"))
    )
    (net (code "62") (name "Net-(JP1-Pad1)") (class "Default")
      (node (ref "JP1") (pin "1") (pinfunction "1_1") (pintype "passive"))
      (node (ref "R35") (pin "2") (pinfunction "2_2") (pintype "passive"))
    )
    (net (code "63") (name "Net-(JP5-Pad1)") (class "Default")
      (node (ref "JP5") (pin "1") (pinfunction "1_1") (pintype "passive"))
      (node (ref "R52") (pin "2") (pinfunction "2_2") (pintype "passive"))
    )
    (net (code "64") (name "Net-(P4-Pad2)") (class "Default")
      (node (ref "P4") (pin "2") (pinfunction "2_2") (pintype "passive"))
      (node (ref "R61") (pin "2") (pinfunction "2_2") (pintype "passive"))
    )
    (net (code "65") (name "Net-(P4-Pad3)") (class "Default")
      (node (ref "P4") (pin "3") (pinfunction "3_3") (pintype "passive"))
      (node (ref "R62") (pin "2") (pinfunction "2_2") (pintype "passive"))
    )
    (net (code "66") (name "Net-(P6-Pad2)") (class "Default")
      (node (ref "P6") (pin "2") (pinfunction "2_2") (pintype "passive"))
      (node (ref "R78") (pin "2") (pinfunction "2_2") (pintype "passive"))
    )
    (net (code "67") (name "Net-(P6-Pad3)") (class "Default")
      (node (ref "P6") (pin "3") (pinfunction "3_3") (pintype "passive"))
      (node (ref "R79") (pin "2") (pinfunction "2_2") (pintype "passive"))
    )
    (net (code "68") (name "Net-(Q1-B)") (class "Default")
      (node (ref "Q1") (pin "1") (pinfunction "B_1") (pintype "passive"))
      (node (ref "R4") (pin "1") (pinfunction "1_1") (pintype "passive"))
      (node (ref "R9") (pin "1") (pinfunction "1_1") (pintype "passive"))
    )
    (net (code "69") (name "Net-(Q1-C)") (class "Default")
      (node (ref "Q1") (pin "3") (pinfunction "C_3") (pintype "passive"))
      (node (ref "R6") (pin "1") (pinfunction "1_1") (pintype "passive"))
    )
    (net (code "70") (name "Net-(Q2-B)") (class "Default")
      (node (ref "Q2") (pin "1") (pinfunction "B_1") (pintype "passive"))
      (node (ref "R12") (pin "1") (pinfunction "1_1") (pintype "passive"))
      (node (ref "R5") (pin "1") (pinfunction "1_1") (pintype "passive"))
    )
    (net (code "71") (name "Net-(Q2-C)") (class "Default")
      (node (ref "Q2") (pin "3") (pinfunction "C_3") (pintype "passive"))
      (node (ref "R7") (pin "1") (pinfunction "1_1") (pintype "passive"))
    )
    (net (code "72") (name "Net-(Q3-B)") (class "Default")
      (node (ref "Q3") (pin "1") (pinfunction "B_1") (pintype "passive"))
      (node (ref "R17") (pin "2") (pinfunction "2_2") (pintype "passive"))
    )
    (net (code "73") (name "Net-(Q3-E)") (class "Default")
      (node (ref "Q3") (pin "2") (pinfunction "E_2") (pintype "passive"))
      (node (ref "R8") (pin "1") (pinfunction "1_1") (pintype "passive"))
    )
    (net (code "74") (name "Net-(Q4-B)") (class "Default")
      (node (ref "Q4") (pin "1") (pinfunction "B_1") (pintype "passive"))
      (node (ref "R14") (pin "1") (pinfunction "1_1") (pintype "passive"))
    )
    (net (code "75") (name "Net-(Q4-C)") (class "Default")
      (node (ref "Q4") (pin "3") (pinfunction "C_3") (pintype "passive"))
      (node (ref "R13") (pin "2") (pinfunction "2_2") (pintype "passive"))
    )
    (net (code "76") (name "Net-(Q5-G)") (class "Default")
      (node (ref "Q5") (pin "1") (pinfunction "G_1") (pintype "passive"))
      (node (ref "R13") (pin "1") (pinfunction "1_1") (pintype "passive"))
      (node (ref "R22") (pin "1") (pinfunction "1_1") (pintype "passive"))
    )
    (net (code "77") (name "Net-(Q6-B)") (class "Default")
      (node (ref "Q6") (pin "1") (pinfunction "B_1") (pintype "passive"))
      (node (ref "R19") (pin "2") (pinfunction "2_2") (pintype "passive"))
    )
    (net (code "78") (name "Net-(Q6-C)") (class "Default")
      (node (ref "Q6") (pin "3") (pinfunction "C_3") (pintype "passive"))
      (node (ref "R9") (pin "2") (pinfunction "2_2") (pintype "passive"))
    )
    (net (code "79") (name "Net-(Q7-B)") (class "Default")
      (node (ref "Q7") (pin "1") (pinfunction "B_1") (pintype "passive"))
      (node (ref "R20") (pin "2") (pinfunction "2_2") (pintype "passive"))
    )
    (net (code "80") (name "Net-(Q7-C)") (class "Default")
      (node (ref "Q7") (pin "3") (pinfunction "C_3") (pintype "passive"))
      (node (ref "R12") (pin "2") (pinfunction "2_2") (pintype "passive"))
    )
    (net (code "81") (name "Net-(Q8-B)") (class "Default")
      (node (ref "C4") (pin "1") (pinfunction "1_1") (pintype "passive"))
      (node (ref "Q8") (pin "1") (pinfunction "B_1") (pintype "passive"))
      (node (ref "R21") (pin "1") (pinfunction "1_1") (pintype "passive"))
      (node (ref "R24") (pin "2") (pinfunction "2_2") (pintype "passive"))
    )
    (net (code "82") (name "Net-(Q9-D)") (class "Default")
      (node (ref "D3") (pin "1") (pinfunction "1_1") (pintype "passive"))
      (node (ref "Q9") (pin "3") (pinfunction "D_3") (pintype "passive"))
    )
    (net (code "83") (name "Net-(Q9-G)") (class "Default")
      (node (ref "Q9") (pin "1") (pinfunction "G_1") (pintype "passive"))
      (node (ref "R33") (pin "2") (pinfunction "2_2") (pintype "passive"))
      (node (ref "R42") (pin "2") (pinfunction "2_2") (pintype "passive"))
    )
    (net (code "84") (name "Net-(Q10-B)") (class "Default")
      (node (ref "Q10") (pin "1") (pinfunction "B_1") (pintype "passive"))
      (node (ref "R50") (pin "1") (pinfunction "1_1") (pintype "passive"))
    )
    (net (code "85") (name "Net-(Q10-C)") (class "Default")
      (node (ref "Q10") (pin "3") (pinfunction "C_3") (pintype "passive"))
      (node (ref "R37") (pin "2") (pinfunction "2_2") (pintype "passive"))
    )
    (net (code "86") (name "Net-(Q11-G)") (class "Default")
      (node (ref "Q11") (pin "1") (pinfunction "G_1") (pintype "passive"))
      (node (ref "R37") (pin "1") (pinfunction "1_1") (pintype "passive"))
      (node (ref "R54") (pin "1") (pinfunction "1_1") (pintype "passive"))
    )
    (net (code "87") (name "Net-(Q12-B)") (class "Default")
      (node (ref "Q12") (pin "1") (pinfunction "B_1") (pintype "passive"))
      (node (ref "R53") (pin "2") (pinfunction "2_2") (pintype "passive"))
    )
    (net (code "88") (name "Net-(Q12-C)") (class "Default")
      (node (ref "Q12") (pin "3") (pinfunction "C_3") (pintype "passive"))
      (node (ref "R42") (pin "1") (pinfunction "1_1") (pintype "passive"))
    )
    (net (code "89") (name "Net-(Q13-D)") (class "Default")
      (node (ref "D6") (pin "1") (pinfunction "1_1") (pintype "passive"))
      (node (ref "Q13") (pin "3") (pinfunction "D_3") (pintype "passive"))
    )
    (net (code "90") (name "Net-(Q13-G)") (class "Default")
      (node (ref "Q13") (pin "1") (pinfunction "G_1") (pintype "passive"))
      (node (ref "R39") (pin "2") (pinfunction "2_2") (pintype "passive"))
      (node (ref "R44") (pin "2") (pinfunction "2_2") (pintype "passive"))
    )
    (net (code "91") (name "Net-(Q14-B)") (class "Default")
      (node (ref "Q14") (pin "1") (pinfunction "B_1") (pintype "passive"))
      (node (ref "R46") (pin "2") (pinfunction "2_2") (pintype "passive"))
    )
    (net (code "92") (name "Net-(Q14-C)") (class "Default")
      (node (ref "Q14") (pin "3") (pinfunction "C_3") (pintype "passive"))
      (node (ref "R44") (pin "1") (pinfunction "1_1") (pintype "passive"))
    )
    (net (code "93") (name "Net-(Q15-D)") (class "Default")
      (node (ref "D10") (pin "1") (pinfunction "1_1") (pintype "passive"))
      (node (ref "Q15") (pin "3") (pinfunction "D_3") (pintype "passive"))
    )
    (net (code "94") (name "Net-(Q15-G)") (class "Default")
      (node (ref "Q15") (pin "1") (pinfunction "G_1") (pintype "passive"))
      (node (ref "R67") (pin "2") (pinfunction "2_2") (pintype "passive"))
      (node (ref "R68") (pin "2") (pinfunction "2_2") (pintype "passive"))
    )
    (net (code "95") (name "Net-(Q16-B)") (class "Default")
      (node (ref "Q16") (pin "1") (pinfunction "B_1") (pintype "passive"))
      (node (ref "R69") (pin "2") (pinfunction "2_2") (pintype "passive"))
    )
    (net (code "96") (name "Net-(Q16-C)") (class "Default")
      (node (ref "Q16") (pin "3") (pinfunction "C_3") (pintype "passive"))
      (node (ref "R68") (pin "1") (pinfunction "1_1") (pintype "passive"))
    )
    (net (code "97") (name "Net-(Q17-D)") (class "Default")
      (node (ref "D4") (pin "1") (pinfunction "1_1") (pintype "passive"))
      (node (ref "Q17") (pin "3") (pinfunction "D_3") (pintype "passive"))
    )
    (net (code "98") (name "Net-(Q17-G)") (class "Default")
      (node (ref "Q17") (pin "1") (pinfunction "G_1") (pintype "passive"))
      (node (ref "R80") (pin "2") (pinfunction "2_2") (pintype "passive"))
      (node (ref "R81") (pin "2") (pinfunction "2_2") (pintype "passive"))
    )
    (net (code "99") (name "Net-(Q18-B)") (class "Default")
      (node (ref "Q18") (pin "1") (pinfunction "B_1") (pintype "passive"))
      (node (ref "R82") (pin "2") (pinfunction "2_2") (pintype "passive"))
    )
    (net (code "100") (name "Net-(Q18-C)") (class "Default")
      (node (ref "Q18") (pin "3") (pinfunction "C_3") (pintype "passive"))
      (node (ref "R81") (pin "1") (pinfunction "1_1") (pintype "passive"))
    )
    (net (code "101") (name "Net-(R29-Pad2)") (class "Default")
      (node (ref "R29") (pin "2") (pinfunction "2_2") (pintype "passive"))
      (node (ref "R30") (pin "1") (pinfunction "1_1") (pintype "passive"))
    )
    (net (code "102") (name "Net-(R57-Pad2)") (class "Default")
      (node (ref "R57") (pin "2") (pinfunction "2_2") (pintype "passive"))
      (node (ref "R58") (pin "1") (pinfunction "1_1") (pintype "passive"))
    )
    (net (code "103") (name "Net-(R72-Pad2)") (class "Default")
      (node (ref "R72") (pin "2") (pinfunction "2_2") (pintype "passive"))
      (node (ref "R73") (pin "1") (pinfunction "1_1") (pintype "passive"))
    )
    (net (code "104") (name "Net-(U1-Vin+)") (class "Default")
      (node (ref "C3") (pin "2") (pinfunction "2_2") (pintype "passive"))
      (node (ref "R23") (pin "2") (pinfunction "2_2") (pintype "passive"))
      (node (ref "U1") (pin "8") (pinfunction "Vin+_8") (pintype "passive"))
    )
    (net (code "105") (name "Net-(U1-Vin-)") (class "Default")
      (node (ref "C3") (pin "1") (pinfunction "1_1") (pintype "passive"))
      (node (ref "R10") (pin "2") (pinfunction "2_2") (pintype "passive"))
      (node (ref "U1") (pin "7") (pinfunction "Vin-_7") (pintype "passive"))
    )
    (net (code "106") (name "Net-(U2-BOOT)") (class "Default")
      (node (ref "C5") (pin "2") (pinfunction "2_2") (pintype "passive"))
      (node (ref "U2") (pin "1") (pinfunction "BOOT_1") (pintype "passive"))
    )
    (net (code "107") (name "Net-(U2-PH)") (class "Default")
      (node (ref "C5") (pin "1") (pinfunction "1_1") (pintype "passive"))
      (node (ref "D5") (pin "2") (pinfunction "2_2") (pintype "passive"))
      (node (ref "L1") (pin "1") (pinfunction "1_1") (pintype "passive"))
      (node (ref "U2") (pin "8") (pinfunction "PH_8") (pintype "passive"))
    )
    (net (code "108") (name "Net-(U2-VSNS)") (class "Default")
      (node (ref "R30") (pin "2") (pinfunction "2_2") (pintype "passive"))
      (node (ref "R31") (pin "1") (pinfunction "1_1") (pintype "passive"))
      (node (ref "U2") (pin "4") (pinfunction "VSNS_4") (pintype "passive"))
    )
    (net (code "109") (name "Net-(U3-BOOT)") (class "Default")
      (node (ref "C8") (pin "2") (pinfunction "2_2") (pintype "passive"))
      (node (ref "U3") (pin "1") (pinfunction "BOOT_1") (pintype "passive"))
    )
    (net (code "110") (name "Net-(U3-PH)") (class "Default")
      (node (ref "C8") (pin "1") (pinfunction "1_1") (pintype "passive"))
      (node (ref "D7") (pin "2") (pinfunction "2_2") (pintype "passive"))
      (node (ref "L2") (pin "1") (pinfunction "1_1") (pintype "passive"))
      (node (ref "U3") (pin "8") (pinfunction "PH_8") (pintype "passive"))
    )
    (net (code "111") (name "Net-(U3-VSNS)") (class "Default")
      (node (ref "R43") (pin "1") (pinfunction "1_1") (pintype "passive"))
      (node (ref "R73") (pin "2") (pinfunction "2_2") (pintype "passive"))
      (node (ref "U3") (pin "4") (pinfunction "VSNS_4") (pintype "passive"))
    )
    (net (code "112") (name "Net-(U4-BOOT)") (class "Default")
      (node (ref "C11") (pin "2") (pinfunction "2_2") (pintype "passive"))
      (node (ref "U4") (pin "1") (pinfunction "BOOT_1") (pintype "passive"))
    )
    (net (code "113") (name "Net-(U4-PH)") (class "Default")
      (node (ref "C11") (pin "1") (pinfunction "1_1") (pintype "passive"))
      (node (ref "D8") (pin "2") (pinfunction "2_2") (pintype "passive"))
      (node (ref "L3") (pin "1") (pinfunction "1_1") (pintype "passive"))
      (node (ref "U4") (pin "8") (pinfunction "PH_8") (pintype "passive"))
    )
    (net (code "114") (name "Net-(U4-VSNS)") (class "Default")
      (node (ref "R58") (pin "2") (pinfunction "2_2") (pintype "passive"))
      (node (ref "R59") (pin "2") (pinfunction "2_2") (pintype "passive"))
      (node (ref "U4") (pin "4") (pinfunction "VSNS_4") (pintype "passive"))
    )
    (net (code "115") (name "Net-(U7-Vin+)") (class "Default")
      (node (ref "C25") (pin "2") (pinfunction "2_2") (pintype "passive"))
      (node (ref "R55") (pin "2") (pinfunction "2_2") (pintype "passive"))
      (node (ref "U7") (pin "8") (pinfunction "Vin+_8") (pintype "passive"))
    )
    (net (code "116") (name "Net-(U7-Vin-)") (class "Default")
      (node (ref "C25") (pin "1") (pinfunction "1_1") (pintype "passive"))
      (node (ref "R36") (pin "2") (pinfunction "2_2") (pintype "passive"))
      (node (ref "U7") (pin "7") (pinfunction "Vin-_7") (pintype "passive"))
    )
    (net (code "117") (name "VIN_5V") (class "Default")
      (node (ref "C14") (pin "1") (pinfunction "1_1") (pintype "passive"))
      (node (ref "C16") (pin "1") (pinfunction "1_1") (pintype "passive"))
      (node (ref "L3") (pin "2") (pinfunction "2_2") (pintype "passive"))
      (node (ref "R56") (pin "2") (pinfunction "2_2") (pintype "passive"))
      (node (ref "R59") (pin "1") (pinfunction "1_1") (pintype "passive"))
      (node (ref "U5") (pin "2") (pinfunction "Vin_2") (pintype "passive"))
    )
    (net (code "118") (name "VIN_24V") (class "Default")
      (node (ref "C12") (pin "1") (pinfunction "1_1") (pintype "passive"))
      (node (ref "C13") (pin "1") (pinfunction "1_1") (pintype "passive"))
      (node (ref "C6") (pin "1") (pinfunction "1_1") (pintype "passive"))
      (node (ref "C9") (pin "1") (pinfunction "1_1") (pintype "passive"))
      (node (ref "JP2") (pin "1") (pinfunction "1_1") (pintype "passive"))
      (node (ref "JP3") (pin "1") (pinfunction "1_1") (pintype "passive"))
      (node (ref "U2") (pin "7") (pinfunction "VIN_7") (pintype "passive"))
      (node (ref "U3") (pin "7") (pinfunction "VIN_7") (pintype "passive"))
      (node (ref "U4") (pin "7") (pinfunction "VIN_7") (pintype "passive"))
    )
    (net (code "119") (name "unconnected-(P5-Pad1)") (class "Default")
      (node (ref "P5") (pin "1") (pinfunction "1_1") (pintype "passive+no_connect"))
    )
    (net (code "120") (name "unconnected-(P6-Pad1)") (class "Default")
      (node (ref "P6") (pin "1") (pinfunction "1_1") (pintype "passive+no_connect"))
    )
    (net (code "121") (name "unconnected-(U2-ENA-Pad5)") (class "Default")
      (node (ref "U2") (pin "5") (pinfunction "ENA_5") (pintype "passive+no_connect"))
    )
    (net (code "122") (name "unconnected-(U2-NC-Pad2)") (class "Default")
      (node (ref "U2") (pin "2") (pinfunction "NC_2") (pintype "passive+no_connect"))
    )
    (net (code "123") (name "unconnected-(U2-NC-Pad3)") (class "Default")
      (node (ref "U2") (pin "3") (pinfunction "NC_3") (pintype "passive+no_connect"))
    )
    (net (code "124") (name "unconnected-(U3-ENA-Pad5)") (class "Default")
      (node (ref "U3") (pin "5") (pinfunction "ENA_5") (pintype "passive+no_connect"))
    )
    (net (code "125") (name "unconnected-(U3-NC-Pad2)") (class "Default")
      (node (ref "U3") (pin "2") (pinfunction "NC_2") (pintype "passive+no_connect"))
    )
    (net (code "126") (name "unconnected-(U3-NC-Pad3)") (class "Default")
      (node (ref "U3") (pin "3") (pinfunction "NC_3") (pintype "passive+no_connect"))
    )
    (net (code "127") (name "unconnected-(U4-ENA-Pad5)") (class "Default")
      (node (ref "U4") (pin "5") (pinfunction "ENA_5") (pintype "passive+no_connect"))
    )
    (net (code "128") (name "unconnected-(U4-NC-Pad2)") (class "Default")
      (node (ref "U4") (pin "2") (pinfunction "NC_2") (pintype "passive+no_connect"))
    )
    (net (code "129") (name "unconnected-(U4-NC-Pad3)") (class "Default")
      (node (ref "U4") (pin "3") (pinfunction "NC_3") (pintype "passive+no_connect"))
    )
  )
)
